# VertMount.net
KiCad netlist of a schematic drawn in EAGLE
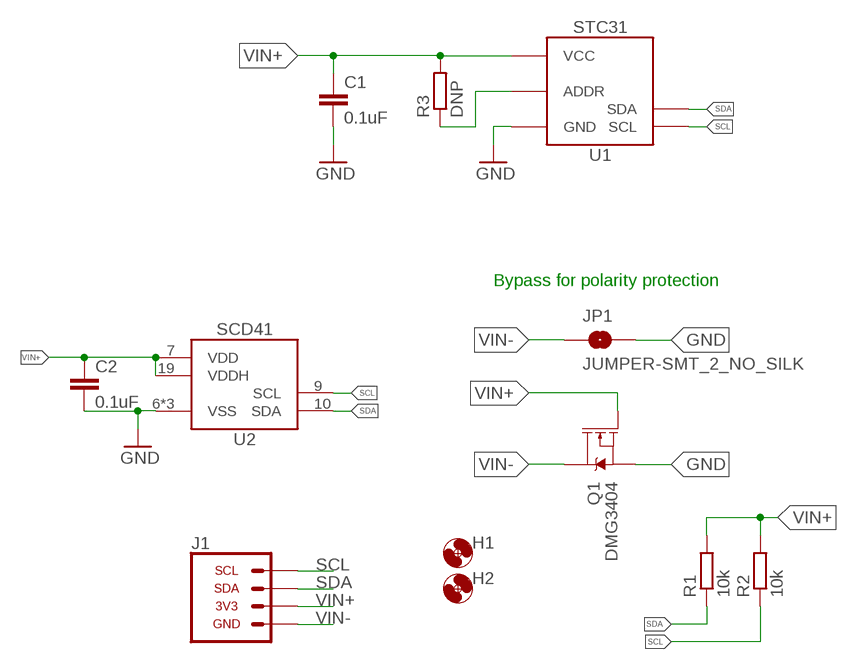
[diagram p0: schematic, sheet 1]

(export (version "E")
  (design (tool "Eeschema 10.0.6"))
  (components
    (comp (ref "C1")
      (value "0.1uF")
      (footprint "eagle-import:C0603")
      (fields (field (name "MF") "Murata") (field (name "MPN") "GCM188R71E104KA57D"))
      (libsource (lib "eagle-import") (part "C-EUC06030.1UF"))
    )
    (comp (ref "C2")
      (value "0.1uF")
      (footprint "eagle-import:C0603")
      (fields (field (name "MF") "Murata") (field (name "MPN") "GCM188R71E104KA57D"))
      (libsource (lib "eagle-import") (part "C-EUC06030.1UF"))
    )
    (comp (ref "H1")
      (value "MOUNTING_HOLE1_NP")
      (footprint "eagle-import:1_72")
      (fields (field (name "MPN") "DNP"))
      (libsource (lib "eagle-import") (part "MOUNTING_HOLE1_NP"))
    )
    (comp (ref "H2")
      (value "MOUNTING_HOLE1_NP")
      (footprint "eagle-import:1_72")
      (fields (field (name "MPN") "DNP"))
      (libsource (lib "eagle-import") (part "MOUNTING_HOLE1_NP"))
    )
    (comp (ref "J1")
      (value "CONN_I2C_SENSOR_BOARD_MOUNT_TH")
      (footprint "eagle-import:1X04_M12_TE_T41400")
      (fields (field (name "MF") "TE") (field (name "MPN") "T4140012041-000"))
      (libsource (lib "eagle-import") (part "CONN_I2C_SENSOR_BOARD_MOUNT_TH"))
    )
    (comp (ref "JP1")
      (value "JUMPER-SMT_2_NO_SILK")
      (footprint "eagle-import:SMT-JUMPER_2_NO_SILK")
      (libsource (lib "eagle-import") (part "JUMPER-SMT_2_NO_SILK"))
    )
    (comp (ref "Q1")
      (value "DMG3404")
      (footprint "eagle-import:SOT23-3")
      (fields (field (name "MF") "Diodes Incorporated") (field (name "MPN") "DMG3404L-7"))
      (libsource (lib "eagle-import") (part "MOSFET-NCH-DMG3404L"))
    )
    (comp (ref "R1")
      (value "10k")
      (footprint "eagle-import:R0603")
      (fields (field (name "MF") "Yageo") (field (name "MPN") "RC0603FR-0710KL"))
      (libsource (lib "eagle-import") (part "R-EU_R060310K"))
    )
    (comp (ref "R2")
      (value "10k")
      (footprint "eagle-import:R0603")
      (fields (field (name "MF") "Yageo") (field (name "MPN") "RC0603FR-0710KL"))
      (libsource (lib "eagle-import") (part "R-EU_R060310K"))
    )
    (comp (ref "R3")
      (value "DNP")
      (footprint "eagle-import:R0603")
      (fields (field (name "MF") "Yageo"))
      (libsource (lib "eagle-import") (part "R-EU_R0603"))
    )
    (comp (ref "U1")
      (value "STC31")
      (footprint "eagle-import:STC31")
      (fields (field (name "DISP") "STC31") (field (name "MF") "Sensirion") (field (name "MPN") "STC31-C-R3"))
      (libsource (lib "eagle-import") (part "STC31"))
    )
    (comp (ref "U2")
      (value "SCD41")
      (footprint "eagle-import:SCD4X")
      (fields (field (name "DISP") "SCD41") (field (name "MF") "Sensirion") (field (name "MPN") "SCD41-D-R2"))
      (libsource (lib "eagle-import") (part "SCD41"))
    )
  )
  (nets
    (net (code "1") (name "GND") (class "Default")
      (node (ref "C1") (pin "2") (pinfunction "2_2") (pintype "passive"))
      (node (ref "C2") (pin "2") (pinfunction "2_2") (pintype "passive"))
      (node (ref "JP1") (pin "2") (pinfunction "2_2") (pintype "passive"))
      (node (ref "Q1") (pin "2") (pinfunction "S_2") (pintype "bidirectional"))
      (node (ref "U1") (pin "1") (pinfunction "GND_1") (pintype "power_in"))
      (node (ref "U1") (pin "11") (pinfunction "GND_11") (pintype "power_in"))
      (node (ref "U1") (pin "5") (pinfunction "GND_5") (pintype "power_in"))
      (node (ref "U1") (pin "9") (pinfunction "GND_9") (pintype "power_in"))
      (node (ref "U1") (pin "EP") (pinfunction "GND_EP") (pintype "power_in"))
      (node (ref "U2") (pin "20") (pinfunction "VSS_20") (pintype "power_in"))
      (node (ref "U2") (pin "6") (pinfunction "VSS_6") (pintype "power_in"))
      (node (ref "U2") (pin "EP") (pinfunction "VSS_EP") (pintype "power_in"))
    )
    (net (code "2") (name "Net-(U1-ADDR)") (class "Default")
      (node (ref "R3") (pin "1") (pinfunction "1_1") (pintype "passive"))
      (node (ref "U1") (pin "3") (pinfunction "ADDR_3") (pintype "input"))
    )
    (net (code "3") (name "SCL") (class "Default")
      (node (ref "J1") (pin "3") (pinfunction "SCL_3") (pintype "passive"))
      (node (ref "R2") (pin "1") (pinfunction "1_1") (pintype "passive"))
      (node (ref "U1") (pin "4") (pinfunction "SCL_4") (pintype "input"))
      (node (ref "U2") (pin "9") (pinfunction "SCL_9") (pintype "input"))
    )
    (net (code "4") (name "SDA") (class "Default")
      (node (ref "J1") (pin "1") (pinfunction "SDA_1") (pintype "passive"))
      (node (ref "R1") (pin "1") (pinfunction "1_1") (pintype "passive"))
      (node (ref "U1") (pin "7") (pinfunction "SDA_7") (pintype "bidirectional"))
      (node (ref "U2") (pin "10") (pinfunction "SDA_10") (pintype "bidirectional"))
    )
    (net (code "5") (name "VIN+") (class "Default")
      (node (ref "C1") (pin "1") (pinfunction "1_1") (pintype "passive"))
      (node (ref "C2") (pin "1") (pinfunction "1_1") (pintype "passive"))
      (node (ref "J1") (pin "2") (pinfunction "3V3_2") (pintype "passive"))
      (node (ref "Q1") (pin "1") (pinfunction "G_1") (pintype "bidirectional"))
      (node (ref "R1") (pin "2") (pinfunction "2_2") (pintype "passive"))
      (node (ref "R2") (pin "2") (pinfunction "2_2") (pintype "passive"))
      (node (ref "R3") (pin "2") (pinfunction "2_2") (pintype "passive"))
      (node (ref "U1") (pin "6") (pinfunction "VCC_6") (pintype "power_in"))
      (node (ref "U2") (pin "19") (pinfunction "VDDH_19") (pintype "power_in"))
      (node (ref "U2") (pin "7") (pinfunction "VDD_7") (pintype "power_in"))
    )
    (net (code "6") (name "VIN-") (class "Default")
      (node (ref "J1") (pin "4") (pinfunction "GND_4") (pintype "passive"))
      (node (ref "JP1") (pin "1") (pinfunction "1_1") (pintype "passive"))
      (node (ref "Q1") (pin "3") (pinfunction "D_3") (pintype "bidirectional"))
    )
  )
)
